# TestBench_rev2.net
KiCad netlist of a schematic drawn in EAGLE
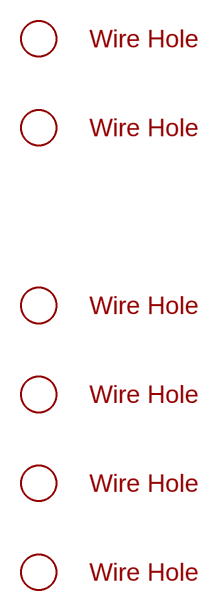
[diagram p0: schematic, sheet 1, part 1 of 2]
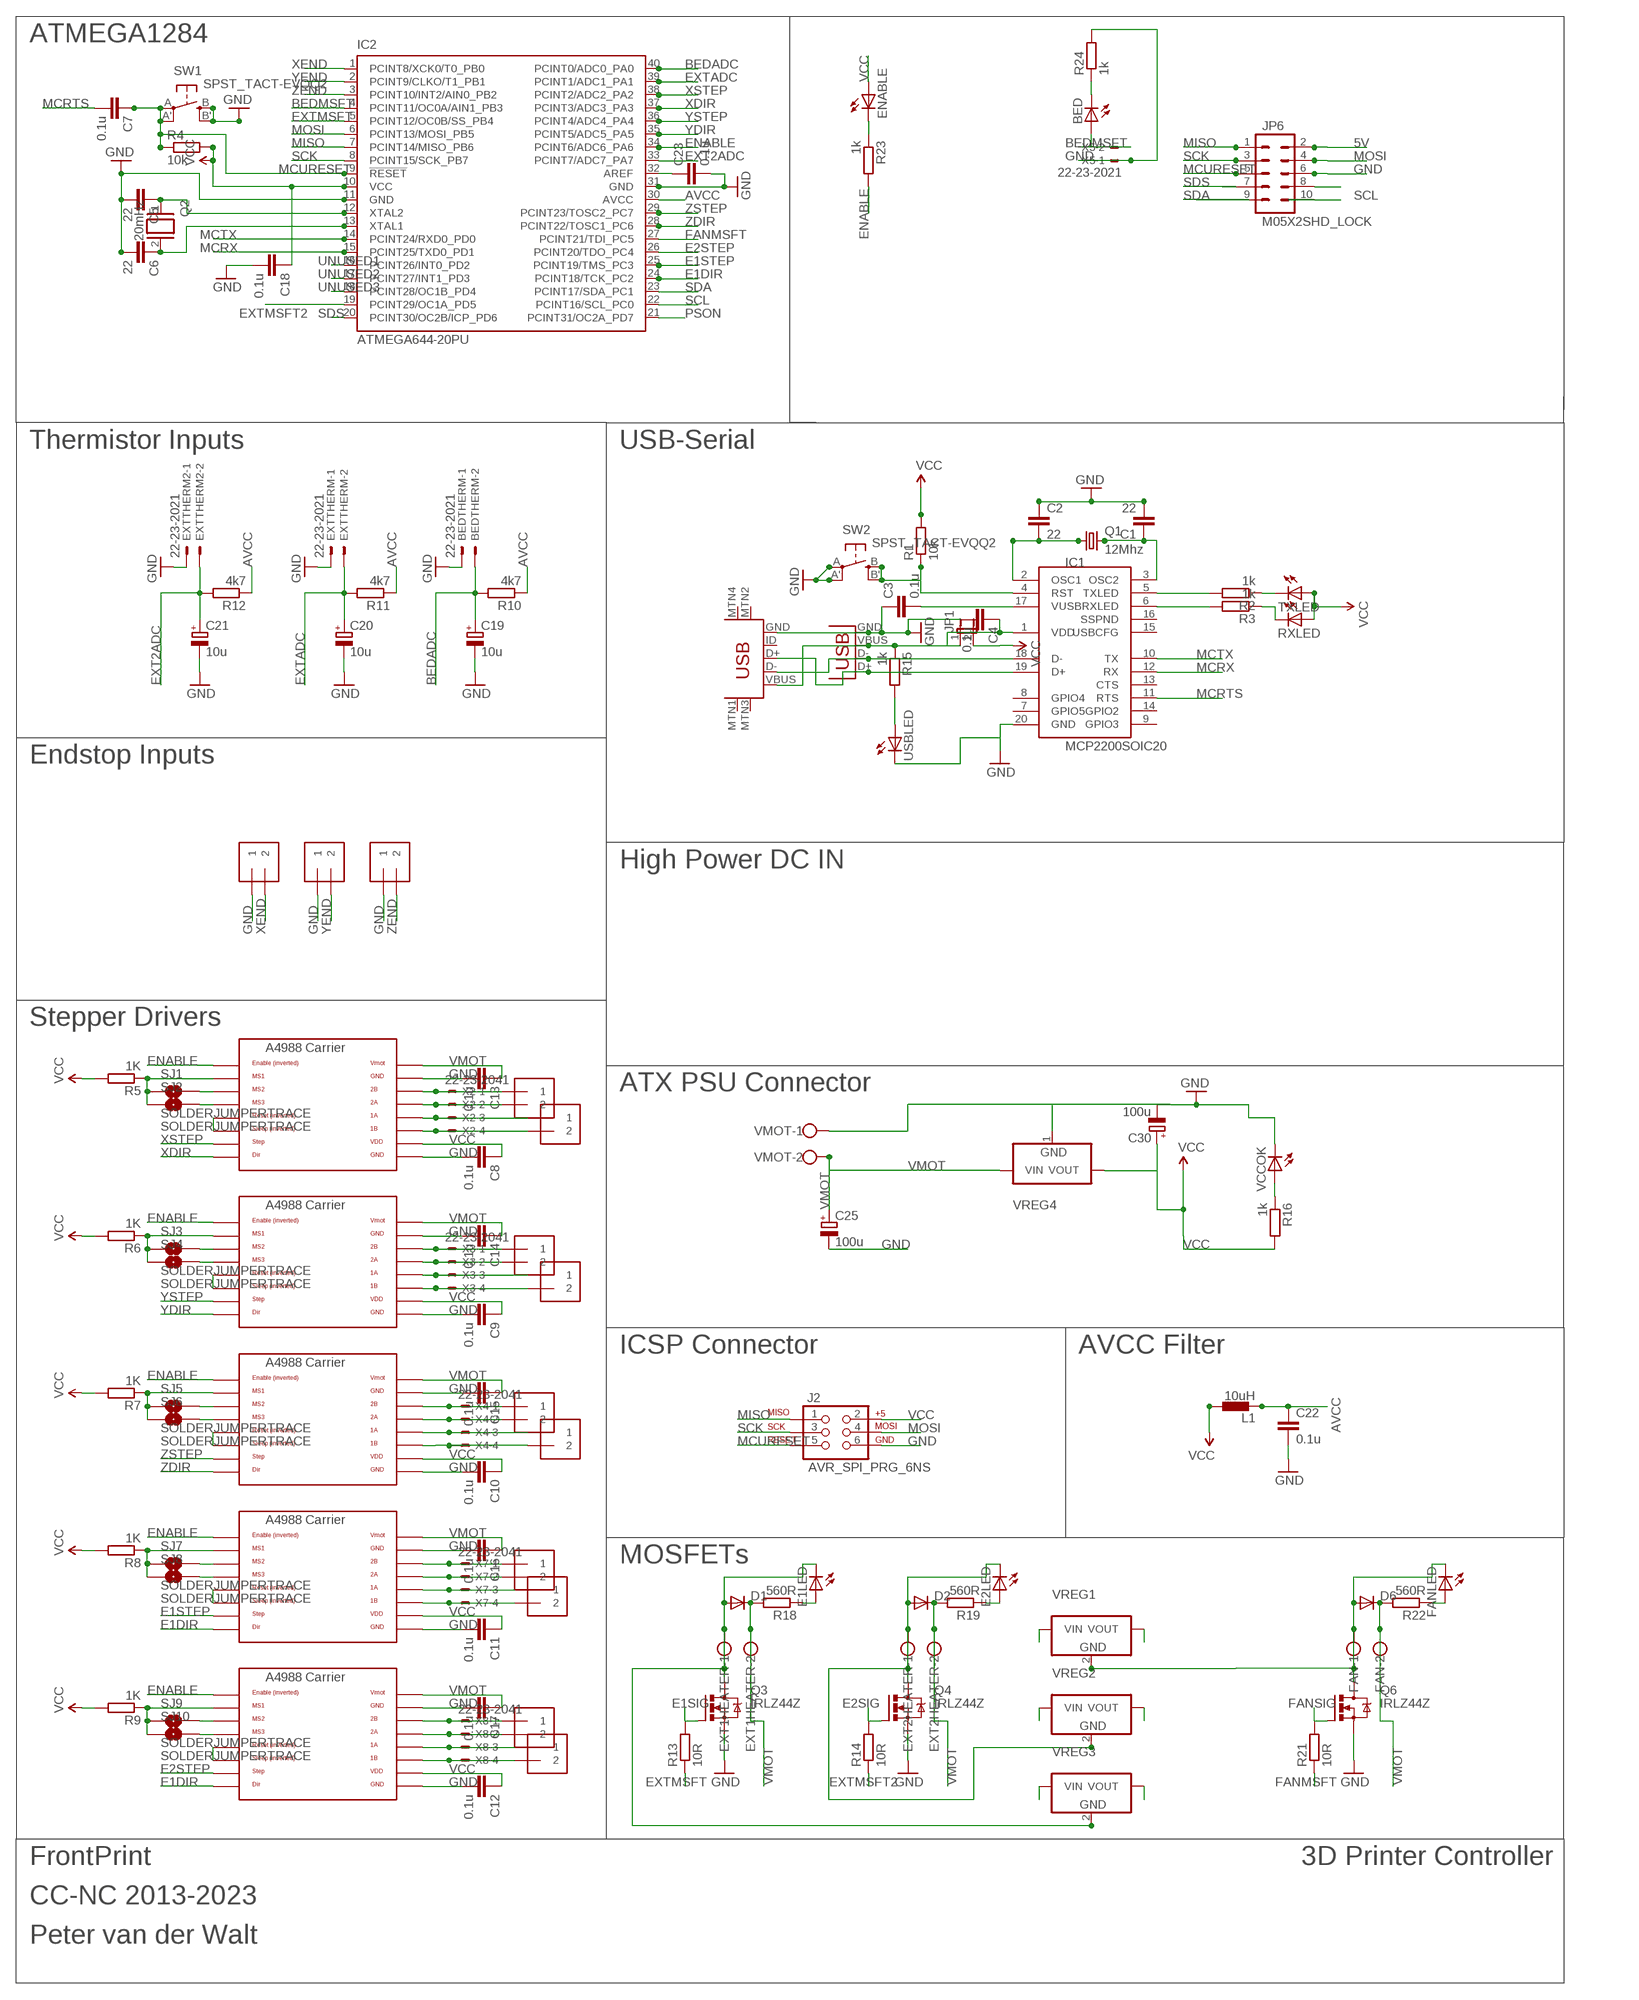
[diagram p1: schematic, sheet 1, part 2 of 2]

(export (version "E")
  (design (tool "Eeschema 10.0.6"))
  (components
    (comp (ref "BED")
      (value "LEDSMT1206")
      (footprint "eagle-import:1206")
      (libsource (lib "eagle-import") (part "LEDSMT1206"))
    )
    (comp (ref "BEDTHERM")
      (value "22-23-2021")
      (footprint "eagle-import:22-23-2021")
      (fields (field (name "MF") "MOLEX"))
      (libsource (lib "eagle-import") (part "22-23-2021"))
    )
    (comp (ref "C1")
      (value "22")
      (footprint "eagle-import:1206")
      (libsource (lib "eagle-import") (part "CAP1206"))
    )
    (comp (ref "C2")
      (value "22")
      (footprint "eagle-import:1206")
      (libsource (lib "eagle-import") (part "CAP1206"))
    )
    (comp (ref "C3")
      (value "0.1u")
      (footprint "eagle-import:1206")
      (libsource (lib "eagle-import") (part "CAP1206"))
    )
    (comp (ref "C4")
      (value "0.1u")
      (footprint "eagle-import:1206")
      (libsource (lib "eagle-import") (part "CAP1206"))
    )
    (comp (ref "C5")
      (value "22")
      (footprint "eagle-import:CAP-PTH-SMALL-KIT")
      (libsource (lib "eagle-import") (part "CAPKIT"))
    )
    (comp (ref "C6")
      (value "22")
      (footprint "eagle-import:CAP-PTH-SMALL-KIT")
      (libsource (lib "eagle-import") (part "CAPKIT"))
    )
    (comp (ref "C7")
      (value "0.1u")
      (footprint "eagle-import:1206")
      (libsource (lib "eagle-import") (part "CAP1206"))
    )
    (comp (ref "C8")
      (value "0.1u")
      (footprint "eagle-import:1206")
      (libsource (lib "eagle-import") (part "CAP1206"))
    )
    (comp (ref "C9")
      (value "0.1u")
      (footprint "eagle-import:1206")
      (libsource (lib "eagle-import") (part "CAP1206"))
    )
    (comp (ref "C10")
      (value "0.1u")
      (footprint "eagle-import:1206")
      (libsource (lib "eagle-import") (part "CAP1206"))
    )
    (comp (ref "C11")
      (value "0.1u")
      (footprint "eagle-import:1206")
      (libsource (lib "eagle-import") (part "CAP1206"))
    )
    (comp (ref "C12")
      (value "0.1u")
      (footprint "eagle-import:1206")
      (libsource (lib "eagle-import") (part "CAP1206"))
    )
    (comp (ref "C13")
      (value "0.1u")
      (footprint "eagle-import:1206")
      (libsource (lib "eagle-import") (part "CAP1206"))
    )
    (comp (ref "C14")
      (value "0.1u")
      (footprint "eagle-import:1206")
      (libsource (lib "eagle-import") (part "CAP1206"))
    )
    (comp (ref "C15")
      (value "0.1u")
      (footprint "eagle-import:1206")
      (libsource (lib "eagle-import") (part "CAP1206"))
    )
    (comp (ref "C16")
      (value "0.1u")
      (footprint "eagle-import:1206")
      (libsource (lib "eagle-import") (part "CAP1206"))
    )
    (comp (ref "C17")
      (value "0.1u")
      (footprint "eagle-import:1206")
      (libsource (lib "eagle-import") (part "CAP1206"))
    )
    (comp (ref "C18")
      (value "0.1u")
      (footprint "eagle-import:1206")
      (libsource (lib "eagle-import") (part "CAP1206"))
    )
    (comp (ref "C19")
      (value "10u")
      (footprint "eagle-import:E2,5-5")
      (libsource (lib "eagle-import") (part "CPOL-EUE2.5-5"))
    )
    (comp (ref "C20")
      (value "10u")
      (footprint "eagle-import:E2,5-5")
      (libsource (lib "eagle-import") (part "CPOL-EUE2.5-5"))
    )
    (comp (ref "C21")
      (value "10u")
      (footprint "eagle-import:E2,5-5")
      (libsource (lib "eagle-import") (part "CPOL-EUE2.5-5"))
    )
    (comp (ref "C22")
      (value "0.1u")
      (footprint "eagle-import:1206")
      (libsource (lib "eagle-import") (part "CAP1206"))
    )
    (comp (ref "C23")
      (value "0.1u")
      (footprint "eagle-import:1206")
      (libsource (lib "eagle-import") (part "CAP1206"))
    )
    (comp (ref "C25")
      (value "100u")
      (footprint "eagle-import:E5-8,5")
      (libsource (lib "eagle-import") (part "CPOL-EUE5-8.5"))
    )
    (comp (ref "C30")
      (value "100u")
      (footprint "eagle-import:E5-8,5")
      (libsource (lib "eagle-import") (part "CPOL-EUE5-8.5"))
    )
    (comp (ref "D1")
      (value "DIODE1N4148")
      (footprint "eagle-import:DIODE-1N4148")
      (libsource (lib "eagle-import") (part "DIODE1N4148"))
    )
    (comp (ref "D2")
      (value "DIODE1N4148")
      (footprint "eagle-import:DIODE-1N4148")
      (libsource (lib "eagle-import") (part "DIODE1N4148"))
    )
    (comp (ref "D6")
      (value "DIODE1N4148")
      (footprint "eagle-import:DIODE-1N4148")
      (libsource (lib "eagle-import") (part "DIODE1N4148"))
    )
    (comp (ref "E1LED")
      (value "LEDSMT1206")
      (footprint "eagle-import:1206")
      (libsource (lib "eagle-import") (part "LEDSMT1206"))
    )
    (comp (ref "E1MOT1")
      (value "1X2-3.5MM")
      (footprint "eagle-import:1X2-3.5MM")
      (libsource (lib "eagle-import") (part "1X2-3.5MM"))
    )
    (comp (ref "E1MOT2")
      (value "1X2-3.5MM")
      (footprint "eagle-import:1X2-3.5MM")
      (libsource (lib "eagle-import") (part "1X2-3.5MM"))
    )
    (comp (ref "E2LED")
      (value "LEDSMT1206")
      (footprint "eagle-import:1206")
      (libsource (lib "eagle-import") (part "LEDSMT1206"))
    )
    (comp (ref "E2MOT1")
      (value "1X2-3.5MM")
      (footprint "eagle-import:1X2-3.5MM")
      (libsource (lib "eagle-import") (part "1X2-3.5MM"))
    )
    (comp (ref "E2MOT2")
      (value "1X2-3.5MM")
      (footprint "eagle-import:1X2-3.5MM")
      (libsource (lib "eagle-import") (part "1X2-3.5MM"))
    )
    (comp (ref "ENABLE")
      (value "LEDSMT1206")
      (footprint "eagle-import:1206")
      (libsource (lib "eagle-import") (part "LEDSMT1206"))
    )
    (comp (ref "EPOLOLU")
      (value "POLOLU_A4983CARRIER")
      (footprint "eagle-import:A4988BREAKOUT")
      (libsource (lib "eagle-import") (part "POLOLU_A4983CARRIER"))
    )
    (comp (ref "EPOLOLU2")
      (value "POLOLU_A4983CARRIER")
      (footprint "eagle-import:A4988BREAKOUT")
      (libsource (lib "eagle-import") (part "POLOLU_A4983CARRIER"))
    )
    (comp (ref "EXT1HEATER")
      (value "W237-102")
      (footprint "eagle-import:W237-102")
      (fields (field (name "MPN") "237-102"))
      (libsource (lib "eagle-import") (part "W237-102"))
    )
    (comp (ref "EXT2HEATER")
      (value "W237-102")
      (footprint "eagle-import:W237-102")
      (fields (field (name "MPN") "237-102"))
      (libsource (lib "eagle-import") (part "W237-102"))
    )
    (comp (ref "EXTTHERM")
      (value "22-23-2021")
      (footprint "eagle-import:22-23-2021")
      (fields (field (name "MF") "MOLEX"))
      (libsource (lib "eagle-import") (part "22-23-2021"))
    )
    (comp (ref "EXTTHERM2")
      (value "22-23-2021")
      (footprint "eagle-import:22-23-2021")
      (fields (field (name "MF") "MOLEX"))
      (libsource (lib "eagle-import") (part "22-23-2021"))
    )
    (comp (ref "FAN")
      (value "W237-102")
      (footprint "eagle-import:W237-102")
      (fields (field (name "MPN") "237-102"))
      (libsource (lib "eagle-import") (part "W237-102"))
    )
    (comp (ref "FANLED")
      (value "LEDSMT1206")
      (footprint "eagle-import:1206")
      (libsource (lib "eagle-import") (part "LEDSMT1206"))
    )
    (comp (ref "IC1")
      (value "MCP2200SOIC20")
      (footprint "eagle-import:SOIC20")
      (libsource (lib "eagle-import") (part "MCP2200SOIC20"))
    )
    (comp (ref "IC2")
      (value "ATMEGA644-20PU")
      (footprint "eagle-import:DIL40")
      (libsource (lib "eagle-import") (part "ATMEGA644-PU20"))
    )
    (comp (ref "J2")
      (value "AVR_SPI_PRG_6NS")
      (footprint "eagle-import:2X3-NS")
      (libsource (lib "eagle-import") (part "AVR_SPI_PRG_6NS"))
    )
    (comp (ref "JP1")
      (value "JUMPER-2PTH_LOCK")
      (footprint "eagle-import:1X02_LOCK")
      (libsource (lib "eagle-import") (part "JUMPER-2PTH_LOCK"))
    )
    (comp (ref "JP6")
      (value "M05X2SHD_LOCK")
      (footprint "eagle-import:2X5-SHROUDED_LOCK")
      (libsource (lib "eagle-import") (part "M05X2SHD_LOCK"))
    )
    (comp (ref "L1")
      (value "10uH")
      (footprint "eagle-import:BL01RN1A")
      (libsource (lib "eagle-import") (part "BL01RN1A"))
    )
    (comp (ref "Q1")
      (value "12Mhz")
      (footprint "eagle-import:HC49UP")
      (libsource (lib "eagle-import") (part "CRYSTALHC49UP"))
    )
    (comp (ref "Q2")
      (value "20mHz")
      (footprint "eagle-import:QS")
      (libsource (lib "eagle-import") (part "XTAL/S"))
    )
    (comp (ref "Q3")
      (value "IRLZ44Z")
      (footprint "eagle-import:TO220BH")
      (libsource (lib "eagle-import") (part "IRLZ44Z"))
    )
    (comp (ref "Q4")
      (value "IRLZ44Z")
      (footprint "eagle-import:TO220BH")
      (libsource (lib "eagle-import") (part "IRLZ44Z"))
    )
    (comp (ref "Q6")
      (value "IRLZ44Z")
      (footprint "eagle-import:TO220BH")
      (libsource (lib "eagle-import") (part "IRLZ44Z"))
    )
    (comp (ref "R1")
      (value "10k")
      (footprint "eagle-import:M1206")
      (libsource (lib "eagle-import") (part "R-EU_M1206"))
    )
    (comp (ref "R2")
      (value "1k")
      (footprint "eagle-import:M1206")
      (libsource (lib "eagle-import") (part "R-EU_M1206"))
    )
    (comp (ref "R3")
      (value "1k")
      (footprint "eagle-import:M1206")
      (libsource (lib "eagle-import") (part "R-EU_M1206"))
    )
    (comp (ref "R4")
      (value "10k")
      (footprint "eagle-import:M1206")
      (libsource (lib "eagle-import") (part "R-EU_M1206"))
    )
    (comp (ref "R5")
      (value "1K")
      (footprint "eagle-import:M1206")
      (libsource (lib "eagle-import") (part "R-EU_M1206"))
    )
    (comp (ref "R6")
      (value "1K")
      (footprint "eagle-import:M1206")
      (libsource (lib "eagle-import") (part "R-EU_M1206"))
    )
    (comp (ref "R7")
      (value "1K")
      (footprint "eagle-import:M1206")
      (libsource (lib "eagle-import") (part "R-EU_M1206"))
    )
    (comp (ref "R8")
      (value "1K")
      (footprint "eagle-import:M1206")
      (libsource (lib "eagle-import") (part "R-EU_M1206"))
    )
    (comp (ref "R9")
      (value "1K")
      (footprint "eagle-import:M1206")
      (libsource (lib "eagle-import") (part "R-EU_M1206"))
    )
    (comp (ref "R10")
      (value "4k7")
      (footprint "eagle-import:M1206")
      (libsource (lib "eagle-import") (part "R-EU_M1206"))
    )
    (comp (ref "R11")
      (value "4k7")
      (footprint "eagle-import:M1206")
      (libsource (lib "eagle-import") (part "R-EU_M1206"))
    )
    (comp (ref "R12")
      (value "4k7")
      (footprint "eagle-import:M1206")
      (libsource (lib "eagle-import") (part "R-EU_M1206"))
    )
    (comp (ref "R13")
      (value "10R")
      (footprint "eagle-import:M1206")
      (libsource (lib "eagle-import") (part "R-EU_M1206"))
    )
    (comp (ref "R14")
      (value "10R")
      (footprint "eagle-import:M1206")
      (libsource (lib "eagle-import") (part "R-EU_M1206"))
    )
    (comp (ref "R15")
      (value "1k")
      (footprint "eagle-import:M1206")
      (libsource (lib "eagle-import") (part "R-EU_M1206"))
    )
    (comp (ref "R16")
      (value "1k")
      (footprint "eagle-import:M1206")
      (libsource (lib "eagle-import") (part "R-EU_M1206"))
    )
    (comp (ref "R18")
      (value "560R")
      (footprint "eagle-import:M1206")
      (libsource (lib "eagle-import") (part "R-EU_M1206"))
    )
    (comp (ref "R19")
      (value "560R")
      (footprint "eagle-import:M1206")
      (libsource (lib "eagle-import") (part "R-EU_M1206"))
    )
    (comp (ref "R21")
      (value "10R")
      (footprint "eagle-import:M1206")
      (libsource (lib "eagle-import") (part "R-EU_M1206"))
    )
    (comp (ref "R22")
      (value "560R")
      (footprint "eagle-import:M1206")
      (libsource (lib "eagle-import") (part "R-EU_M1206"))
    )
    (comp (ref "R23")
      (value "1k")
      (footprint "eagle-import:M1206")
      (libsource (lib "eagle-import") (part "R-EU_M1206"))
    )
    (comp (ref "R24")
      (value "1k")
      (footprint "eagle-import:M1206")
      (libsource (lib "eagle-import") (part "R-EU_M1206"))
    )
    (comp (ref "RXLED")
      (value "LEDSMT1206")
      (footprint "eagle-import:1206")
      (libsource (lib "eagle-import") (part "LEDSMT1206"))
    )
    (comp (ref "SJ1")
      (value "SOLDERJUMPERTRACE")
      (footprint "eagle-import:SJ_2S-TRACE")
      (libsource (lib "eagle-import") (part "SOLDERJUMPERTRACE"))
    )
    (comp (ref "SJ2")
      (value "SOLDERJUMPERTRACE")
      (footprint "eagle-import:SJ_2S-TRACE")
      (libsource (lib "eagle-import") (part "SOLDERJUMPERTRACE"))
    )
    (comp (ref "SJ3")
      (value "SOLDERJUMPERTRACE")
      (footprint "eagle-import:SJ_2S-TRACE")
      (libsource (lib "eagle-import") (part "SOLDERJUMPERTRACE"))
    )
    (comp (ref "SJ4")
      (value "SOLDERJUMPERTRACE")
      (footprint "eagle-import:SJ_2S-TRACE")
      (libsource (lib "eagle-import") (part "SOLDERJUMPERTRACE"))
    )
    (comp (ref "SJ5")
      (value "SOLDERJUMPERTRACE")
      (footprint "eagle-import:SJ_2S-TRACE")
      (libsource (lib "eagle-import") (part "SOLDERJUMPERTRACE"))
    )
    (comp (ref "SJ6")
      (value "SOLDERJUMPERTRACE")
      (footprint "eagle-import:SJ_2S-TRACE")
      (libsource (lib "eagle-import") (part "SOLDERJUMPERTRACE"))
    )
    (comp (ref "SJ7")
      (value "SOLDERJUMPERTRACE")
      (footprint "eagle-import:SJ_2S-TRACE")
      (libsource (lib "eagle-import") (part "SOLDERJUMPERTRACE"))
    )
    (comp (ref "SJ8")
      (value "SOLDERJUMPERTRACE")
      (footprint "eagle-import:SJ_2S-TRACE")
      (libsource (lib "eagle-import") (part "SOLDERJUMPERTRACE"))
    )
    (comp (ref "SJ9")
      (value "SOLDERJUMPERTRACE")
      (footprint "eagle-import:SJ_2S-TRACE")
      (libsource (lib "eagle-import") (part "SOLDERJUMPERTRACE"))
    )
    (comp (ref "SJ10")
      (value "SOLDERJUMPERTRACE")
      (footprint "eagle-import:SJ_2S-TRACE")
      (libsource (lib "eagle-import") (part "SOLDERJUMPERTRACE"))
    )
    (comp (ref "SW1")
      (value "SPST_TACT-EVQQ2")
      (footprint "eagle-import:EVQ-Q2")
      (libsource (lib "eagle-import") (part "SPST_TACT-EVQQ2"))
    )
    (comp (ref "SW2")
      (value "SPST_TACT-EVQQ2")
      (footprint "eagle-import:EVQ-Q2")
      (libsource (lib "eagle-import") (part "SPST_TACT-EVQQ2"))
    )
    (comp (ref "TXLED")
      (value "LEDSMT1206")
      (footprint "eagle-import:1206")
      (libsource (lib "eagle-import") (part "LEDSMT1206"))
    )
    (comp (ref "U$1")
      (value "3MMHOLE")
      (footprint "eagle-import:3MMHOLE")
      (libsource (lib "eagle-import") (part "3MMHOLE"))
    )
    (comp (ref "U$2")
      (value "USB-MINIB-5PIN")
      (footprint "eagle-import:USB-MINIB")
      (libsource (lib "eagle-import") (part "USB-MINIB-5PIN"))
    )
    (comp (ref "U$3")
      (value "3MMHOLE")
      (footprint "eagle-import:3MMHOLE")
      (libsource (lib "eagle-import") (part "3MMHOLE"))
    )
    (comp (ref "U$5")
      (value "3MMHOLE")
      (footprint "eagle-import:3MMHOLE")
      (libsource (lib "eagle-import") (part "3MMHOLE"))
    )
    (comp (ref "U$6")
      (value "3MMHOLE")
      (footprint "eagle-import:3MMHOLE")
      (libsource (lib "eagle-import") (part "3MMHOLE"))
    )
    (comp (ref "U$7")
      (value "3MMHOLE")
      (footprint "eagle-import:3MMHOLE")
      (libsource (lib "eagle-import") (part "3MMHOLE"))
    )
    (comp (ref "U$8")
      (value "3MMHOLE")
      (footprint "eagle-import:3MMHOLE")
      (libsource (lib "eagle-import") (part "3MMHOLE"))
    )
    (comp (ref "USBLED")
      (value "LEDSMT1206")
      (footprint "eagle-import:1206")
      (libsource (lib "eagle-import") (part "LEDSMT1206"))
    )
    (comp (ref "VCCOK")
      (value "LEDSMT1206")
      (footprint "eagle-import:1206")
      (libsource (lib "eagle-import") (part "LEDSMT1206"))
    )
    (comp (ref "VMOT")
      (value "W237-102")
      (footprint "eagle-import:W237-102")
      (fields
        (field (name "MPN") "237-102")
        (field (name "MPN_1") "237-102")
        (field (name "OC_FARNELL") "unknown")
        (field (name "OC_NEWARK") "70K9898")
      )
      (libsource (lib "eagle-import") (part "W237-102"))
    )
    (comp (ref "VREG1")
      (value "VREG_3PINS-D2PAK")
      (footprint "eagle-import:D2PAK")
      (libsource (lib "eagle-import") (part "VREG_3PINS-D2PAK"))
    )
    (comp (ref "VREG2")
      (value "VREG_3PINS-D2PAK")
      (footprint "eagle-import:D2PAK")
      (libsource (lib "eagle-import") (part "VREG_3PINS-D2PAK"))
    )
    (comp (ref "VREG3")
      (value "VREG_3PINS-D2PAK")
      (footprint "eagle-import:D2PAK")
      (libsource (lib "eagle-import") (part "VREG_3PINS-D2PAK"))
    )
    (comp (ref "VREG4")
      (value "VREG_3PINS-DPAK")
      (footprint "eagle-import:DPAK")
      (libsource (lib "eagle-import") (part "VREG_3PINS-DPAK"))
    )
    (comp (ref "X1")
      (value "USBPTH")
      (footprint "eagle-import:USB-B-PTH")
      (libsource (lib "eagle-import") (part "USBPTH"))
    )
    (comp (ref "X2")
      (value "22-23-2041")
      (footprint "eagle-import:22-23-2041")
      (fields (field (name "MF") "MOLEX"))
      (libsource (lib "eagle-import") (part "22-23-2041"))
    )
    (comp (ref "X3")
      (value "22-23-2041")
      (footprint "eagle-import:22-23-2041")
      (fields (field (name "MF") "MOLEX"))
      (libsource (lib "eagle-import") (part "22-23-2041"))
    )
    (comp (ref "X4")
      (value "22-23-2041")
      (footprint "eagle-import:22-23-2041")
      (fields (field (name "MF") "MOLEX"))
      (libsource (lib "eagle-import") (part "22-23-2041"))
    )
    (comp (ref "X5")
      (value "22-23-2021")
      (footprint "eagle-import:22-23-2021")
      (fields (field (name "MF") "MOLEX"))
      (libsource (lib "eagle-import") (part "22-23-2021"))
    )
    (comp (ref "X7")
      (value "22-23-2041")
      (footprint "eagle-import:22-23-2041")
      (fields (field (name "MF") "MOLEX"))
      (libsource (lib "eagle-import") (part "22-23-2041"))
    )
    (comp (ref "X8")
      (value "22-23-2041")
      (footprint "eagle-import:22-23-2041")
      (fields (field (name "MF") "MOLEX"))
      (libsource (lib "eagle-import") (part "22-23-2041"))
    )
    (comp (ref "XEND")
      (value "1X2-3.5MM")
      (footprint "eagle-import:1X2-3.5MM")
      (libsource (lib "eagle-import") (part "1X2-3.5MM"))
    )
    (comp (ref "XMOT1")
      (value "1X2-3.5MM")
      (footprint "eagle-import:1X2-3.5MM")
      (libsource (lib "eagle-import") (part "1X2-3.5MM"))
    )
    (comp (ref "XMOT2")
      (value "1X2-3.5MM")
      (footprint "eagle-import:1X2-3.5MM")
      (libsource (lib "eagle-import") (part "1X2-3.5MM"))
    )
    (comp (ref "XPOLOLU")
      (value "POLOLU_A4983CARRIER")
      (footprint "eagle-import:A4988BREAKOUT")
      (libsource (lib "eagle-import") (part "POLOLU_A4983CARRIER"))
    )
    (comp (ref "YEND")
      (value "1X2-3.5MM")
      (footprint "eagle-import:1X2-3.5MM")
      (libsource (lib "eagle-import") (part "1X2-3.5MM"))
    )
    (comp (ref "YMOT1")
      (value "1X2-3.5MM")
      (footprint "eagle-import:1X2-3.5MM")
      (libsource (lib "eagle-import") (part "1X2-3.5MM"))
    )
    (comp (ref "YMOT2")
      (value "1X2-3.5MM")
      (footprint "eagle-import:1X2-3.5MM")
      (libsource (lib "eagle-import") (part "1X2-3.5MM"))
    )
    (comp (ref "YPOLOLU")
      (value "POLOLU_A4983CARRIER")
      (footprint "eagle-import:A4988BREAKOUT")
      (libsource (lib "eagle-import") (part "POLOLU_A4983CARRIER"))
    )
    (comp (ref "ZEND")
      (value "1X2-3.5MM")
      (footprint "eagle-import:1X2-3.5MM")
      (libsource (lib "eagle-import") (part "1X2-3.5MM"))
    )
    (comp (ref "ZMOT1")
      (value "1X2-3.5MM")
      (footprint "eagle-import:1X2-3.5MM")
      (libsource (lib "eagle-import") (part "1X2-3.5MM"))
    )
    (comp (ref "ZMOT2")
      (value "1X2-3.5MM")
      (footprint "eagle-import:1X2-3.5MM")
      (libsource (lib "eagle-import") (part "1X2-3.5MM"))
    )
    (comp (ref "ZPOLOLU")
      (value "POLOLU_A4983CARRIER")
      (footprint "eagle-import:A4988BREAKOUT")
      (libsource (lib "eagle-import") (part "POLOLU_A4983CARRIER"))
    )
  )
  (nets
    (net (code "1") (name "/5V") (class "Default")
      (node (ref "JP6") (pin "2") (pinfunction "2_2") (pintype "passive"))
    )
    (net (code "2") (name "/AVCC") (class "Default")
      (node (ref "C22") (pin "1") (pinfunction "1_1") (pintype "passive"))
      (node (ref "IC2") (pin "30") (pinfunction "AVCC_30") (pintype "power_in"))
      (node (ref "L1") (pin "1") (pinfunction "1_1") (pintype "passive"))
      (node (ref "R10") (pin "1") (pinfunction "1_1") (pintype "passive"))
      (node (ref "R11") (pin "1") (pinfunction "1_1") (pintype "passive"))
      (node (ref "R12") (pin "1") (pinfunction "1_1") (pintype "passive"))
    )
    (net (code "3") (name "/BEDADC") (class "Default")
      (node (ref "BEDTHERM") (pin "2") (pinfunction "S_2") (pintype "passive"))
      (node (ref "C19") (pin "+") (pinfunction "+_+") (pintype "passive"))
      (node (ref "IC2") (pin "40") (pinfunction "PCINT0/ADC0_PA0_40") (pintype "bidirectional"))
      (node (ref "R10") (pin "2") (pinfunction "2_2") (pintype "passive"))
    )
    (net (code "4") (name "/BEDMSFT") (class "Default")
      (node (ref "BED") (pin "A") (pinfunction "A_A") (pintype "passive"))
      (node (ref "IC2") (pin "4") (pinfunction "PCINT11/OC0A/AIN1_PB3_4") (pintype "bidirectional"))
      (node (ref "X5") (pin "2") (pinfunction "S_2") (pintype "passive"))
    )
    (net (code "5") (name "/E1DIR") (class "Default")
      (node (ref "EPOLOLU") (pin "DIR") (pinfunction "DIR_DIR") (pintype "input"))
      (node (ref "EPOLOLU2") (pin "DIR") (pinfunction "DIR_DIR") (pintype "input"))
      (node (ref "IC2") (pin "24") (pinfunction "PCINT18/TCK_PC2_24") (pintype "bidirectional"))
    )
    (net (code "6") (name "/E1SIG") (class "Default")
      (node (ref "Q3") (pin "G") (pinfunction "G_G") (pintype "passive"))
      (node (ref "R13") (pin "2") (pinfunction "2_2") (pintype "passive"))
      (node (ref "VREG3") (pin "1") (pinfunction "VIN_1") (pintype "bidirectional"))
    )
    (net (code "7") (name "/E1STEP") (class "Default")
      (node (ref "EPOLOLU") (pin "STEP") (pinfunction "STEP_STEP") (pintype "input"))
      (node (ref "IC2") (pin "25") (pinfunction "PCINT19/TMS_PC3_25") (pintype "bidirectional"))
    )
    (net (code "8") (name "/E2SIG") (class "Default")
      (node (ref "Q4") (pin "G") (pinfunction "G_G") (pintype "passive"))
      (node (ref "R14") (pin "2") (pinfunction "2_2") (pintype "passive"))
      (node (ref "VREG2") (pin "1") (pinfunction "VIN_1") (pintype "bidirectional"))
    )
    (net (code "9") (name "/E2STEP") (class "Default")
      (node (ref "EPOLOLU2") (pin "STEP") (pinfunction "STEP_STEP") (pintype "input"))
      (node (ref "IC2") (pin "26") (pinfunction "PCINT20/TDO_PC4_26") (pintype "bidirectional"))
    )
    (net (code "10") (name "/ENABLE") (class "Default")
      (node (ref "EPOLOLU") (pin "EN") (pinfunction "EN_EN") (pintype "input"))
      (node (ref "EPOLOLU2") (pin "EN") (pinfunction "EN_EN") (pintype "input"))
      (node (ref "IC2") (pin "34") (pinfunction "PCINT6/ADC6_PA6_34") (pintype "bidirectional"))
      (node (ref "R23") (pin "2") (pinfunction "2_2") (pintype "passive"))
      (node (ref "XPOLOLU") (pin "EN") (pinfunction "EN_EN") (pintype "input"))
      (node (ref "YPOLOLU") (pin "EN") (pinfunction "EN_EN") (pintype "input"))
      (node (ref "ZPOLOLU") (pin "EN") (pinfunction "EN_EN") (pintype "input"))
    )
    (net (code "11") (name "/EXT2ADC") (class "Default")
      (node (ref "C21") (pin "+") (pinfunction "+_+") (pintype "passive"))
      (node (ref "EXTTHERM2") (pin "2") (pinfunction "S_2") (pintype "passive"))
      (node (ref "IC2") (pin "33") (pinfunction "PCINT7/ADC7_PA7_33") (pintype "bidirectional"))
      (node (ref "R12") (pin "2") (pinfunction "2_2") (pintype "passive"))
    )
    (net (code "12") (name "/EXTADC") (class "Default")
      (node (ref "C20") (pin "+") (pinfunction "+_+") (pintype "passive"))
      (node (ref "EXTTHERM") (pin "2") (pinfunction "S_2") (pintype "passive"))
      (node (ref "IC2") (pin "39") (pinfunction "PCINT1/ADC1_PA1_39") (pintype "bidirectional"))
      (node (ref "R11") (pin "2") (pinfunction "2_2") (pintype "passive"))
    )
    (net (code "13") (name "/EXTMSFT") (class "Default")
      (node (ref "IC2") (pin "5") (pinfunction "PCINT12/OC0B/SS_PB4_5") (pintype "bidirectional"))
      (node (ref "R13") (pin "1") (pinfunction "1_1") (pintype "passive"))
    )
    (net (code "14") (name "/EXTMSFT2") (class "Default")
      (node (ref "IC2") (pin "19") (pinfunction "PCINT29/OC1A_PD5_19") (pintype "bidirectional"))
      (node (ref "R14") (pin "1") (pinfunction "1_1") (pintype "passive"))
    )
    (net (code "15") (name "/FANMSFT") (class "Default")
      (node (ref "IC2") (pin "27") (pinfunction "PCINT21/TDI_PC5_27") (pintype "bidirectional"))
      (node (ref "R21") (pin "1") (pinfunction "1_1") (pintype "passive"))
    )
    (net (code "16") (name "/FANSIG") (class "Default")
      (node (ref "Q6") (pin "G") (pinfunction "G_G") (pintype "passive"))
      (node (ref "R21") (pin "2") (pinfunction "2_2") (pintype "passive"))
      (node (ref "VREG1") (pin "1") (pinfunction "VIN_1") (pintype "bidirectional"))
    )
    (net (code "17") (name "/MCRTS") (class "Default")
      (node (ref "C7") (pin "2") (pinfunction "2_2") (pintype "passive"))
      (node (ref "IC1") (pin "11") (pinfunction "RTS_11") (pintype "bidirectional"))
    )
    (net (code "18") (name "/MCRX") (class "Default")
      (node (ref "IC1") (pin "12") (pinfunction "RX_12") (pintype "bidirectional"))
      (node (ref "IC2") (pin "15") (pinfunction "PCINT25/TXD0_PD1_15") (pintype "bidirectional"))
    )
    (net (code "19") (name "/MCTX") (class "Default")
      (node (ref "IC1") (pin "10") (pinfunction "TX_10") (pintype "bidirectional"))
      (node (ref "IC2") (pin "14") (pinfunction "PCINT24/RXD0_PD0_14") (pintype "bidirectional"))
    )
    (net (code "20") (name "/MCURESET") (class "Default")
      (node (ref "C7") (pin "1") (pinfunction "1_1") (pintype "passive"))
      (node (ref "IC2") (pin "9") (pinfunction "~{RESET}_9") (pintype "input"))
      (node (ref "J2") (pin "5") (pinfunction "5_5") (pintype "passive"))
      (node (ref "JP6") (pin "5") (pinfunction "5_5") (pintype "passive"))
      (node (ref "R4") (pin "1") (pinfunction "1_1") (pintype "passive"))
      (node (ref "SW1") (pin "A") (pinfunction "P_A") (pintype "passive"))
      (node (ref "SW1") (pin "A'") (pinfunction "P1_A'") (pintype "passive"))
    )
    (net (code "21") (name "/MISO") (class "Default")
      (node (ref "IC2") (pin "7") (pinfunction "PCINT14/MISO_PB6_7") (pintype "bidirectional"))
      (node (ref "J2") (pin "1") (pinfunction "1_1") (pintype "passive"))
      (node (ref "JP6") (pin "1") (pinfunction "1_1") (pintype "passive"))
    )
    (net (code "22") (name "/MOSI") (class "Default")
      (node (ref "IC2") (pin "6") (pinfunction "PCINT13/MOSI_PB5_6") (pintype "bidirectional"))
      (node (ref "J2") (pin "4") (pinfunction "4_4") (pintype "passive"))
      (node (ref "JP6") (pin "4") (pinfunction "4_4") (pintype "passive"))
    )
    (net (code "23") (name "/PSON") (class "Default")
      (node (ref "IC2") (pin "21") (pinfunction "PCINT31/OC2A_PD7_21") (pintype "bidirectional"))
    )
    (net (code "24") (name "/SCK") (class "Default")
      (node (ref "IC2") (pin "8") (pinfunction "PCINT15/SCK_PB7_8") (pintype "bidirectional"))
      (node (ref "J2") (pin "3") (pinfunction "3_3") (pintype "passive"))
      (node (ref "JP6") (pin "3") (pinfunction "3_3") (pintype "passive"))
    )
    (net (code "25") (name "/SCL") (class "Default")
      (node (ref "IC2") (pin "22") (pinfunction "PCINT16/SCL_PC0_22") (pintype "bidirectional"))
      (node (ref "JP6") (pin "10") (pinfunction "10_10") (pintype "passive"))
    )
    (net (code "26") (name "/SDA") (class "Default")
      (node (ref "IC2") (pin "23") (pinfunction "PCINT17/SDA_PC1_23") (pintype "bidirectional"))
      (node (ref "JP6") (pin "9") (pinfunction "9_9") (pintype "passive"))
    )
    (net (code "27") (name "/SDS") (class "Default")
      (node (ref "IC2") (pin "20") (pinfunction "PCINT30/OC2B/ICP_PD6_20") (pintype "bidirectional"))
      (node (ref "JP6") (pin "7") (pinfunction "7_7") (pintype "passive"))
    )
    (net (code "28") (name "/UNUSED1") (class "Default")
      (node (ref "IC2") (pin "16") (pinfunction "PCINT26/INT0_PD2_16") (pintype "bidirectional"))
    )
    (net (code "29") (name "/UNUSED2") (class "Default")
      (node (ref "IC2") (pin "17") (pinfunction "PCINT27/INT1_PD3_17") (pintype "bidirectional"))
    )
    (net (code "30") (name "/UNUSED3") (class "Default")
      (node (ref "IC2") (pin "18") (pinfunction "PCINT28/OC1B_PD4_18") (pintype "bidirectional"))
    )
    (net (code "31") (name "/VMOT") (class "Default")
      (node (ref "C13") (pin "1") (pinfunction "1_1") (pintype "passive"))
      (node (ref "C14") (pin "1") (pinfunction "1_1") (pintype "passive"))
      (node (ref "C15") (pin "1") (pinfunction "1_1") (pintype "passive"))
      (node (ref "C16") (pin "1") (pinfunction "1_1") (pintype "passive"))
      (node (ref "C17") (pin "1") (pinfunction "1_1") (pintype "passive"))
      (node (ref "C25") (pin "+") (pinfunction "+_+") (pintype "passive"))
      (node (ref "D1") (pin "C") (pinfunction "C_C") (pintype "passive"))
      (node (ref "D2") (pin "C") (pinfunction "C_C") (pintype "passive"))
      (node (ref "D6") (pin "C") (pinfunction "C_C") (pintype "passive"))
      (node (ref "EPOLOLU") (pin "VMOT") (pinfunction "VMOT_VMOT") (pintype "power_in"))
      (node (ref "EPOLOLU2") (pin "VMOT") (pinfunction "VMOT_VMOT") (pintype "power_in"))
      (node (ref "EXT1HEATER") (pin "2") (pinfunction "KL_2") (pintype "passive"))
      (node (ref "EXT2HEATER") (pin "2") (pinfunction "KL_2") (pintype "passive"))
      (node (ref "FAN") (pin "2") (pinfunction "KL_2") (pintype "passive"))
      (node (ref "R18") (pin "2") (pinfunction "2_2") (pintype "passive"))
      (node (ref "R19") (pin "2") (pinfunction "2_2") (pintype "passive"))
      (node (ref "R22") (pin "2") (pinfunction "2_2") (pintype "passive"))
      (node (ref "VMOT") (pin "2") (pinfunction "KL_2") (pintype "passive"))
      (node (ref "VREG4") (pin "3") (pinfunction "VIN_3") (pintype "bidirectional"))
      (node (ref "XPOLOLU") (pin "VMOT") (pinfunction "VMOT_VMOT") (pintype "power_in"))
      (node (ref "YPOLOLU") (pin "VMOT") (pinfunction "VMOT_VMOT") (pintype "power_in"))
      (node (ref "ZPOLOLU") (pin "VMOT") (pinfunction "VMOT_VMOT") (pintype "power_in"))
    )
    (net (code "32") (name "/XDIR") (class "Default")
      (node (ref "IC2") (pin "37") (pinfunction "PCINT3/ADC3_PA3_37") (pintype "bidirectional"))
      (node (ref "XPOLOLU") (pin "DIR") (pinfunction "DIR_DIR") (pintype "input"))
    )
    (net (code "33") (name "/XEND") (class "Default")
      (node (ref "IC2") (pin "1") (pinfunction "PCINT8/XCK0/T0_PB0_1") (pintype "bidirectional"))
      (node (ref "XEND") (pin "2") (pinfunction "2_2") (pintype "passive"))
    )
    (net (code "34") (name "/XSTEP") (class "Default")
      (node (ref "IC2") (pin "38") (pinfunction "PCINT2/ADC2_PA2_38") (pintype "bidirectional"))
      (node (ref "XPOLOLU") (pin "STEP") (pinfunction "STEP_STEP") (pintype "input"))
    )
    (net (code "35") (name "/YDIR") (class "Default")
      (node (ref "IC2") (pin "35") (pinfunction "PCINT5/ADC5_PA5_35") (pintype "bidirectional"))
      (node (ref "YPOLOLU") (pin "DIR") (pinfunction "DIR_DIR") (pintype "input"))
    )
    (net (code "36") (name "/YEND") (class "Default")
      (node (ref "IC2") (pin "2") (pinfunction "PCINT9/CLKO/T1_PB1_2") (pintype "bidirectional"))
      (node (ref "YEND") (pin "2") (pinfunction "2_2") (pintype "passive"))
    )
    (net (code "37") (name "/YSTEP") (class "Default")
      (node (ref "IC2") (pin "36") (pinfunction "PCINT4/ADC4_PA4_36") (pintype "bidirectional"))
      (node (ref "YPOLOLU") (pin "STEP") (pinfunction "STEP_STEP") (pintype "input"))
    )
    (net (code "38") (name "/ZDIR") (class "Default")
      (node (ref "IC2") (pin "28") (pinfunction "PCINT22/TOSC1_PC6_28") (pintype "bidirectional"))
      (node (ref "ZPOLOLU") (pin "DIR") (pinfunction "DIR_DIR") (pintype "input"))
    )
    (net (code "39") (name "/ZEND") (class "Default")
      (node (ref "IC2") (pin "3") (pinfunction "PCINT10/INT2/AIN0_PB2_3") (pintype "bidirectional"))
      (node (ref "ZEND") (pin "2") (pinfunction "2_2") (pintype "passive"))
    )
    (net (code "40") (name "/ZSTEP") (class "Default")
      (node (ref "IC2") (pin "29") (pinfunction "PCINT23/TOSC2_PC7_29") (pintype "bidirectional"))
      (node (ref "ZPOLOLU") (pin "STEP") (pinfunction "STEP_STEP") (pintype "input"))
    )
    (net (code "41") (name "GND") (class "Default")
      (node (ref "BEDTHERM") (pin "1") (pinfunction "S_1") (pintype "passive"))
      (node (ref "C1") (pin "2") (pinfunction "2_2") (pintype "passive"))
      (node (ref "C10") (pin "2") (pinfunction "2_2") (pintype "passive"))
      (node (ref "C11") (pin "2") (pinfunction "2_2") (pintype "passive"))
      (node (ref "C12") (pin "2") (pinfunction "2_2") (pintype "passive"))
      (node (ref "C13") (pin "2") (pinfunction "2_2") (pintype "passive"))
      (node (ref "C14") (pin "2") (pinfunction "2_2") (pintype "passive"))
      (node (ref "C15") (pin "2") (pinfunction "2_2") (pintype "passive"))
      (node (ref "C16") (pin "2") (pinfunction "2_2") (pintype "passive"))
      (node (ref "C17") (pin "2") (pinfunction "2_2") (pintype "passive"))
      (node (ref "C18") (pin "2") (pinfunction "2_2") (pintype "passive"))
      (node (ref "C19") (pin "-") (pinfunction "-_-") (pintype "passive"))
      (node (ref "C2") (pin "1") (pinfunction "1_1") (pintype "passive"))
      (node (ref "C20") (pin "-") (pinfunction "-_-") (pintype "passive"))
      (node (ref "C21") (pin "-") (pinfunction "-_-") (pintype "passive"))
      (node (ref "C22") (pin "2") (pinfunction "2_2") (pintype "passive"))
      (node (ref "C23") (pin "2") (pinfunction "2_2") (pintype "passive"))
      (node (ref "C25") (pin "-") (pinfunction "-_-") (pintype "passive"))
      (node (ref "C3") (pin "1") (pinfunction "1_1") (pintype "passive"))
      (node (ref "C30") (pin "-") (pinfunction "-_-") (pintype "passive"))
      (node (ref "C4") (pin "2") (pinfunction "2_2") (pintype "passive"))
      (node (ref "C5") (pin "2") (pinfunction "2_2") (pintype "passive"))
      (node (ref "C6") (pin "2") (pinfunction "2_2") (pintype "passive"))
      (node (ref "C8") (pin "2") (pinfunction "2_2") (pintype "passive"))
      (node (ref "C9") (pin "2") (pinfunction "2_2") (pintype "passive"))
      (node (ref "EPOLOLU") (pin "GND") (pinfunction "GND_GND") (pintype "power_in"))
      (node (ref "EPOLOLU") (pin "GND@0") (pinfunction "GND_GND@0") (pintype "power_in"))
      (node (ref "EPOLOLU2") (pin "GND") (pinfunction "GND_GND") (pintype "power_in"))
      (node (ref "EPOLOLU2") (pin "GND@0") (pinfunction "GND_GND@0") (pintype "power_in"))
      (node (ref "EXTTHERM") (pin "1") (pinfunction "S_1") (pintype "passive"))
      (node (ref "EXTTHERM2") (pin "1") (pinfunction "S_1") (pintype "passive"))
      (node (ref "IC1") (pin "20") (pinfunction "GND_20") (pintype "bidirectional"))
      (node (ref "IC2") (pin "11") (pinfunction "GND_11") (pintype "power_in"))
      (node (ref "IC2") (pin "31") (pinfunction "GND_31") (pintype "power_in"))
      (node (ref "J2") (pin "6") (pinfunction "6_6") (pintype "passive"))
      (node (ref "JP6") (pin "6") (pinfunction "6_6") (pintype "passive"))
      (node (ref "Q3") (pin "S") (pinfunction "S_S") (pintype "passive"))
      (node (ref "Q4") (pin "S") (pinfunction "S_S") (pintype "passive"))
      (node (ref "Q6") (pin "S") (pinfunction "S_S") (pintype "passive"))
      (node (ref "R24") (pin "2") (pinfunction "2_2") (pintype "passive"))
      (node (ref "SW1") (pin "B") (pinfunction "S_B") (pintype "passive"))
      (node (ref "SW1") (pin "B'") (pinfunction "S1_B'") (pintype "passive"))
      (node (ref "SW2") (pin "A") (pinfunction "P_A") (pintype "passive"))
      (node (ref "SW2") (pin "A'") (pinfunction "P1_A'") (pintype "passive"))
      (node (ref "U$2") (pin "GND") (pinfunction "GND_GND") (pintype "bidirectional"))
      (node (ref "USBLED") (pin "C") (pinfunction "C_C") (pintype "passive"))
      (node (ref "VCCOK") (pin "C") (pinfunction "C_C") (pintype "passive"))
      (node (ref "VMOT") (pin "1") (pinfunction "KL_1") (pintype "passive"))
      (node (ref "VREG1") (pin "3") (pinfunction "VOUT_3") (pintype "bidirectional"))
      (node (ref "VREG2") (pin "3") (pinfunction "VOUT_3") (pintype "bidirectional"))
      (node (ref "VREG3") (pin "3") (pinfunction "VOUT_3") (pintype "bidirectional"))
      (node (ref "VREG4") (pin "1") (pinfunction "GND_1") (pintype "bidirectional"))
      (node (ref "X1") (pin "GND") (pinfunction "GND_GND") (pintype "bidirectional"))
      (node (ref "X5") (pin "1") (pinfunction "S_1") (pintype "passive"))
      (node (ref "XEND") (pin "1") (pinfunction "1_1") (pintype "passive"))
      (node (ref "XPOLOLU") (pin "GND") (pinfunction "GND_GND") (pintype "power_in"))
      (node (ref "XPOLOLU") (pin "GND@0") (pinfunction "GND_GND@0") (pintype "power_in"))
      (node (ref "YEND") (pin "1") (pinfunction "1_1") (pintype "passive"))
      (node (ref "YPOLOLU") (pin "GND") (pinfunction "GND_GND") (pintype "power_in"))
      (node (ref "YPOLOLU") (pin "GND@0") (pinfunction "GND_GND@0") (pintype "power_in"))
      (node (ref "ZEND") (pin "1") (pinfunction "1_1") (pintype "passive"))
      (node (ref "ZPOLOLU") (pin "GND") (pinfunction "GND_GND") (pintype "power_in"))
      (node (ref "ZPOLOLU") (pin "GND@0") (pinfunction "GND_GND@0") (pintype "power_in"))
    )
    (net (code "42") (name "Net-(BED-PadC)") (class "Default")
      (node (ref "BED") (pin "C") (pinfunction "C_C") (pintype "passive"))
      (node (ref "R24") (pin "1") (pinfunction "1_1") (pintype "passive"))
    )
    (net (code "43") (name "Net-(E1LED-PadA)") (class "Default")
      (node (ref "E1LED") (pin "A") (pinfunction "A_A") (pintype "passive"))
      (node (ref "R18") (pin "1") (pinfunction "1_1") (pintype "passive"))
    )
    (net (code "44") (name "Net-(E2LED-PadA)") (class "Default")
      (node (ref "E2LED") (pin "A") (pinfunction "A_A") (pintype "passive"))
      (node (ref "R19") (pin "1") (pinfunction "1_1") (pintype "passive"))
    )
    (net (code "45") (name "Net-(ENABLE-PadC)") (class "Default")
      (node (ref "ENABLE") (pin "C") (pinfunction "C_C") (pintype "passive"))
      (node (ref "R23") (pin "1") (pinfunction "1_1") (pintype "passive"))
    )
    (net (code "46") (name "Net-(EPOLOLU-PadMS1)") (class "Default")
      (node (ref "EPOLOLU") (pin "MS1") (pinfunction "MS1_MS1") (pintype "input"))
      (node (ref "R8") (pin "1") (pinfunction "1_1") (pintype "passive"))
      (node (ref "SJ7") (pin "1") (pinfunction "1_1") (pintype "passive"))
      (node (ref "SJ8") (pin "1") (pinfunction "1_1") (pintype "passive"))
    )
    (net (code "47") (name "Net-(EPOLOLU-PadMS2)") (class "Default")
      (node (ref "EPOLOLU") (pin "MS2") (pinfunction "MS2_MS2") (pintype "input"))
      (node (ref "SJ7") (pin "2") (pinfunction "2_2") (pintype "passive"))
    )
    (net (code "48") (name "Net-(EPOLOLU-PadMS3)") (class "Default")
      (node (ref "EPOLOLU") (pin "MS3") (pinfunction "MS3_MS3") (pintype "input"))
      (node (ref "SJ8") (pin "2") (pinfunction "2_2") (pintype "passive"))
    )
    (net (code "49") (name "Net-(EPOLOLU-SLEEP)") (class "Default")
      (node (ref "EPOLOLU") (pin "RST") (pinfunction "RST_RST") (pintype "input"))
      (node (ref "EPOLOLU") (pin "SLP") (pinfunction "SLEEP_SLP") (pintype "input"))
    )
    (net (code "50") (name "Net-(EPOLOLU2-PadMS1)") (class "Default")
      (node (ref "EPOLOLU2") (pin "MS1") (pinfunction "MS1_MS1") (pintype "input"))
      (node (ref "R9") (pin "1") (pinfunction "1_1") (pintype "passive"))
      (node (ref "SJ10") (pin "1") (pinfunction "1_1") (pintype "passive"))
      (node (ref "SJ9") (pin "1") (pinfunction "1_1") (pintype "passive"))
    )
    (net (code "51") (name "Net-(EPOLOLU2-PadMS2)") (class "Default")
      (node (ref "EPOLOLU2") (pin "MS2") (pinfunction "MS2_MS2") (pintype "input"))
      (node (ref "SJ9") (pin "2") (pinfunction "2_2") (pintype "passive"))
    )
    (net (code "52") (name "Net-(EPOLOLU2-PadMS3)") (class "Default")
      (node (ref "EPOLOLU2") (pin "MS3") (pinfunction "MS3_MS3") (pintype "input"))
      (node (ref "SJ10") (pin "2") (pinfunction "2_2") (pintype "passive"))
    )
    (net (code "53") (name "Net-(EPOLOLU2-SLEEP)") (class "Default")
      (node (ref "EPOLOLU2") (pin "RST") (pinfunction "RST_RST") (pintype "input"))
      (node (ref "EPOLOLU2") (pin "SLP") (pinfunction "SLEEP_SLP") (pintype "input"))
    )
    (net (code "54") (name "Net-(EXT1HEATERA-KL)") (class "Default")
      (node (ref "D1") (pin "A") (pinfunction "A_A") (pintype "passive"))
      (node (ref "E1LED") (pin "C") (pinfunction "C_C") (pintype "passive"))
      (node (ref "EXT1HEATER") (pin "1") (pinfunction "KL_1") (pintype "passive"))
      (node (ref "Q3") (pin "D") (pinfunction "D_D") (pintype "passive"))
      (node (ref "VREG3") (pin "2") (pinfunction "GND_2") (pintype "bidirectional"))
    )
    (net (code "55") (name "Net-(EXT2HEATERA-KL)") (class "Default")
      (node (ref "D2") (pin "A") (pinfunction "A_A") (pintype "passive"))
      (node (ref "E2LED") (pin "C") (pinfunction "C_C") (pintype "passive"))
      (node (ref "EXT2HEATER") (pin "1") (pinfunction "KL_1") (pintype "passive"))
      (node (ref "Q4") (pin "D") (pinfunction "D_D") (pintype "passive"))
      (node (ref "VREG2") (pin "2") (pinfunction "GND_2") (pintype "bidirectional"))
    )
    (net (code "56") (name "Net-(FANA-KL)") (class "Default")
      (node (ref "D6") (pin "A") (pinfunction "A_A") (pintype "passive"))
      (node (ref "FAN") (pin "1") (pinfunction "KL_1") (pintype "passive"))
      (node (ref "FANLED") (pin "C") (pinfunction "C_C") (pintype "passive"))
      (node (ref "Q6") (pin "D") (pinfunction "D_D") (pintype "passive"))
      (node (ref "VREG1") (pin "2") (pinfunction "GND_2") (pintype "bidirectional"))
    )
    (net (code "57") (name "Net-(FANLED-PadA)") (class "Default")
      (node (ref "FANLED") (pin "A") (pinfunction "A_A") (pintype "passive"))
      (node (ref "R22") (pin "1") (pinfunction "1_1") (pintype "passive"))
    )
    (net (code "58") (name "Net-(IC1-D+)") (class "Default")
      (node (ref "IC1") (pin "19") (pinfunction "D+_19") (pintype "bidirectional"))
      (node (ref "U$2") (pin "D+") (pinfunction "D+_D+") (pintype "bidirectional"))
      (node (ref "X1") (pin "D+") (pinfunction "D+_D+") (pintype "bidirectional"))
    )
    (net (code "59") (name "Net-(IC1-D-)") (class "Default")
      (node (ref "IC1") (pin "18") (pinfunction "D-_18") (pintype "bidirectional"))
      (node (ref "U$2") (pin "D-") (pinfunction "D-_D-") (pintype "bidirectional"))
      (node (ref "X1") (pin "D-") (pinfunction "D-_D-") (pintype "bidirectional"))
    )
    (net (code "60") (name "Net-(IC1-OSC1)") (class "Default")
      (node (ref "C2") (pin "2") (pinfunction "2_2") (pintype "passive"))
      (node (ref "IC1") (pin "2") (pinfunction "OSC1_2") (pintype "bidirectional"))
      (node (ref "Q1") (pin "1") (pinfunction "1_1") (pintype "passive"))
    )
    (net (code "61") (name "Net-(IC1-OSC2)") (class "Default")
      (node (ref "C1") (pin "1") (pinfunction "1_1") (pintype "passive"))
      (node (ref "IC1") (pin "3") (pinfunction "OSC2_3") (pintype "bidirectional"))
      (node (ref "Q1") (pin "2") (pinfunction "2_2") (pintype "passive"))
    )
    (net (code "62") (name "Net-(IC1-RST)") (class "Default")
      (node (ref "IC1") (pin "4") (pinfunction "RST_4") (pintype "bidirectional"))
      (node (ref "R1") (pin "1") (pinfunction "1_1") (pintype "passive"))
      (node (ref "SW2") (pin "B") (pinfunction "S_B") (pintype "passive"))
      (node (ref "SW2") (pin "B'") (pinfunction "S1_B'") (pintype "passive"))
    )
    (net (code "63") (name "Net-(IC1-RXLED)") (class "Default")
      (node (ref "IC1") (pin "6") (pinfunction "RXLED_6") (pintype "bidirectional"))
      (node (ref "R3") (pin "2") (pinfunction "2_2") (pintype "passive"))
    )
    (net (code "64") (name "Net-(IC1-TXLED)") (class "Default")
      (node (ref "IC1") (pin "5") (pinfunction "TXLED_5") (pintype "bidirectional"))
      (node (ref "R2") (pin "2") (pinfunction "2_2") (pintype "passive"))
    )
    (net (code "65") (name "Net-(IC1-VDD)") (class "Default")
      (node (ref "C4") (pin "1") (pinfunction "1_1") (pintype "passive"))
      (node (ref "IC1") (pin "1") (pinfunction "VDD_1") (pintype "bidirectional"))
      (node (ref "JP1") (pin "1") (pinfunction "1_1") (pintype "passive"))
      (node (ref "R15") (pin "1") (pinfunction "1_1") (pintype "passive"))
      (node (ref "U$2") (pin "VBUS") (pinfunction "VBUS_VBUS") (pintype "bidirectional"))
      (node (ref "X1") (pin "VBUS") (pinfunction "VBUS_VBUS") (pintype "bidirectional"))
    )
    (net (code "66") (name "Net-(IC1-VUSB)") (class "Default")
      (node (ref "C3") (pin "2") (pinfunction "2_2") (pintype "passive"))
      (node (ref "IC1") (pin "17") (pinfunction "VUSB_17") (pintype "bidirectional"))
    )
    (net (code "67") (name "Net-(IC2-AREF)") (class "Default")
      (node (ref "C23") (pin "1") (pinfunction "1_1") (pintype "passive"))
      (node (ref "IC2") (pin "32") (pinfunction "AREF_32") (pintype "passive"))
    )
    (net (code "68") (name "Net-(IC2-XTAL1)") (class "Default")
      (node (ref "C6") (pin "1") (pinfunction "1_1") (pintype "passive"))
      (node (ref "IC2") (pin "13") (pinfunction "XTAL1_13") (pintype "input"))
      (node (ref "Q2") (pin "2") (pinfunction "2_2") (pintype "passive"))
    )
    (net (code "69") (name "Net-(IC2-XTAL2)") (class "Default")
      (node (ref "C5") (pin "1") (pinfunction "1_1") (pintype "passive"))
      (node (ref "IC2") (pin "12") (pinfunction "XTAL2_12") (pintype "output"))
      (node (ref "Q2") (pin "1") (pinfunction "1_1") (pintype "passive"))
    )
    (net (code "70") (name "Net-(R2-Pad1)") (class "Default")
      (node (ref "R2") (pin "1") (pinfunction "1_1") (pintype "passive"))
      (node (ref "TXLED") (pin "C") (pinfunction "C_C") (pintype "passive"))
    )
    (net (code "71") (name "Net-(R3-Pad1)") (class "Default")
      (node (ref "R3") (pin "1") (pinfunction "1_1") (pintype "passive"))
      (node (ref "RXLED") (pin "C") (pinfunction "C_C") (pintype "passive"))
    )
    (net (code "72") (name "Net-(R5-Pad1)") (class "Default")
      (node (ref "R5") (pin "1") (pinfunction "1_1") (pintype "passive"))
      (node (ref "SJ1") (pin "1") (pinfunction "1_1") (pintype "passive"))
      (node (ref "SJ2") (pin "1") (pinfunction "1_1") (pintype "passive"))
      (node (ref "XPOLOLU") (pin "MS1") (pinfunction "MS1_MS1") (pintype "input"))
    )
    (net (code "73") (name "Net-(R6-Pad1)") (class "Default")
      (node (ref "R6") (pin "1") (pinfunction "1_1") (pintype "passive"))
      (node (ref "SJ3") (pin "1") (pinfunction "1_1") (pintype "passive"))
      (node (ref "SJ4") (pin "1") (pinfunction "1_1") (pintype "passive"))
      (node (ref "YPOLOLU") (pin "MS1") (pinfunction "MS1_MS1") (pintype "input"))
    )
    (net (code "74") (name "Net-(R7-Pad1)") (class "Default")
      (node (ref "R7") (pin "1") (pinfunction "1_1") (pintype "passive"))
      (node (ref "SJ5") (pin "1") (pinfunction "1_1") (pintype "passive"))
      (node (ref "SJ6") (pin "1") (pinfunction "1_1") (pintype "passive"))
      (node (ref "ZPOLOLU") (pin "MS1") (pinfunction "MS1_MS1") (pintype "input"))
    )
    (net (code "75") (name "Net-(R15-Pad2)") (class "Default")
      (node (ref "R15") (pin "2") (pinfunction "2_2") (pintype "passive"))
      (node (ref "USBLED") (pin "A") (pinfunction "A_A") (pintype "passive"))
    )
    (net (code "76") (name "Net-(R16-Pad1)") (class "Default")
      (node (ref "R16") (pin "1") (pinfunction "1_1") (pintype "passive"))
      (node (ref "VCCOK") (pin "A") (pinfunction "A_A") (pintype "passive"))
    )
    (net (code "77") (name "Net-(SJ1-Pad2)") (class "Default")
      (node (ref "SJ1") (pin "2") (pinfunction "2_2") (pintype "passive"))
      (node (ref "XPOLOLU") (pin "MS2") (pinfunction "MS2_MS2") (pintype "input"))
    )
    (net (code "78") (name "Net-(SJ2-Pad2)") (class "Default")
      (node (ref "SJ2") (pin "2") (pinfunction "2_2") (pintype "passive"))
      (node (ref "XPOLOLU") (pin "MS3") (pinfunction "MS3_MS3") (pintype "input"))
    )
    (net (code "79") (name "Net-(SJ3-Pad2)") (class "Default")
      (node (ref "SJ3") (pin "2") (pinfunction "2_2") (pintype "passive"))
      (node (ref "YPOLOLU") (pin "MS2") (pinfunction "MS2_MS2") (pintype "input"))
    )
    (net (code "80") (name "Net-(SJ4-Pad2)") (class "Default")
      (node (ref "SJ4") (pin "2") (pinfunction "2_2") (pintype "passive"))
      (node (ref "YPOLOLU") (pin "MS3") (pinfunction "MS3_MS3") (pintype "input"))
    )
    (net (code "81") (name "Net-(SJ5-Pad2)") (class "Default")
      (node (ref "SJ5") (pin "2") (pinfunction "2_2") (pintype "passive"))
      (node (ref "ZPOLOLU") (pin "MS2") (pinfunction "MS2_MS2") (pintype "input"))
    )
    (net (code "82") (name "Net-(SJ6-Pad2)") (class "Default")
      (node (ref "SJ6") (pin "2") (pinfunction "2_2") (pintype "passive"))
      (node (ref "ZPOLOLU") (pin "MS3") (pinfunction "MS3_MS3") (pintype "input"))
    )
    (net (code "83") (name "Net-(X2A-S)") (class "Default")
      (node (ref "X2") (pin "1") (pinfunction "S_1") (pintype "passive"))
      (node (ref "XMOT1") (pin "1") (pinfunction "1_1") (pintype "passive"))
      (node (ref "XPOLOLU") (pin "2B") (pinfunction "2B_2B") (pintype "output"))
    )
    (net (code "84") (name "Net-(X2B-S)") (class "Default")
      (node (ref "X2") (pin "2") (pinfunction "S_2") (pintype "passive"))
      (node (ref "XMOT1") (pin "2") (pinfunction "2_2") (pintype "passive"))
      (node (ref "XPOLOLU") (pin "2A") (pinfunction "2A_2A") (pintype "output"))
    )
    (net (code "85") (name "Net-(X2C-S)") (class "Default")
      (node (ref "X2") (pin "3") (pinfunction "S_3") (pintype "passive"))
      (node (ref "XMOT2") (pin "1") (pinfunction "1_1") (pintype "passive"))
      (node (ref "XPOLOLU") (pin "1A") (pinfunction "1A_1A") (pintype "output"))
    )
    (net (code "86") (name "Net-(X2D-S)") (class "Default")
      (node (ref "X2") (pin "4") (pinfunction "S_4") (pintype "passive"))
      (node (ref "XMOT2") (pin "2") (pinfunction "2_2") (pintype "passive"))
      (node (ref "XPOLOLU") (pin "1B") (pinfunction "1B_1B") (pintype "output"))
    )
    (net (code "87") (name "Net-(X3A-S)") (class "Default")
      (node (ref "X3") (pin "1") (pinfunction "S_1") (pintype "passive"))
      (node (ref "YMOT1") (pin "1") (pinfunction "1_1") (pintype "passive"))
      (node (ref "YPOLOLU") (pin "2B") (pinfunction "2B_2B") (pintype "output"))
    )
    (net (code "88") (name "Net-(X3B-S)") (class "Default")
      (node (ref "X3") (pin "2") (pinfunction "S_2") (pintype "passive"))
      (node (ref "YMOT1") (pin "2") (pinfunction "2_2") (pintype "passive"))
      (node (ref "YPOLOLU") (pin "2A") (pinfunction "2A_2A") (pintype "output"))
    )
    (net (code "89") (name "Net-(X3C-S)") (class "Default")
      (node (ref "X3") (pin "3") (pinfunction "S_3") (pintype "passive"))
      (node (ref "YMOT2") (pin "1") (pinfunction "1_1") (pintype "passive"))
      (node (ref "YPOLOLU") (pin "1A") (pinfunction "1A_1A") (pintype "output"))
    )
    (net (code "90") (name "Net-(X3D-S)") (class "Default")
      (node (ref "X3") (pin "4") (pinfunction "S_4") (pintype "passive"))
      (node (ref "YMOT2") (pin "2") (pinfunction "2_2") (pintype "passive"))
      (node (ref "YPOLOLU") (pin "1B") (pinfunction "1B_1B") (pintype "output"))
    )
    (net (code "91") (name "Net-(X4A-S)") (class "Default")
      (node (ref "X4") (pin "1") (pinfunction "S_1") (pintype "passive"))
      (node (ref "ZMOT1") (pin "1") (pinfunction "1_1") (pintype "passive"))
      (node (ref "ZPOLOLU") (pin "2B") (pinfunction "2B_2B") (pintype "output"))
    )
    (net (code "92") (name "Net-(X4B-S)") (class "Default")
      (node (ref "X4") (pin "2") (pinfunction "S_2") (pintype "passive"))
      (node (ref "ZMOT1") (pin "2") (pinfunction "2_2") (pintype "passive"))
      (node (ref "ZPOLOLU") (pin "2A") (pinfunction "2A_2A") (pintype "output"))
    )
    (net (code "93") (name "Net-(X4C-S)") (class "Default")
      (node (ref "X4") (pin "3") (pinfunction "S_3") (pintype "passive"))
      (node (ref "ZMOT2") (pin "1") (pinfunction "1_1") (pintype "passive"))
      (node (ref "ZPOLOLU") (pin "1A") (pinfunction "1A_1A") (pintype "output"))
    )
    (net (code "94") (name "Net-(X4D-S)") (class "Default")
      (node (ref "X4") (pin "4") (pinfunction "S_4") (pintype "passive"))
      (node (ref "ZMOT2") (pin "2") (pinfunction "2_2") (pintype "passive"))
      (node (ref "ZPOLOLU") (pin "1B") (pinfunction "1B_1B") (pintype "output"))
    )
    (net (code "95") (name "Net-(X7A-S)") (class "Default")
      (node (ref "E1MOT1") (pin "1") (pinfunction "1_1") (pintype "passive"))
      (node (ref "EPOLOLU") (pin "2B") (pinfunction "2B_2B") (pintype "output"))
      (node (ref "X7") (pin "1") (pinfunction "S_1") (pintype "passive"))
    )
    (net (code "96") (name "Net-(X7B-S)") (class "Default")
      (node (ref "E1MOT1") (pin "2") (pinfunction "2_2") (pintype "passive"))
      (node (ref "EPOLOLU") (pin "2A") (pinfunction "2A_2A") (pintype "output"))
      (node (ref "X7") (pin "2") (pinfunction "S_2") (pintype "passive"))
    )
    (net (code "97") (name "Net-(X7C-S)") (class "Default")
      (node (ref "E1MOT2") (pin "1") (pinfunction "1_1") (pintype "passive"))
      (node (ref "EPOLOLU") (pin "1A") (pinfunction "1A_1A") (pintype "output"))
      (node (ref "X7") (pin "3") (pinfunction "S_3") (pintype "passive"))
    )
    (net (code "98") (name "Net-(X7D-S)") (class "Default")
      (node (ref "E1MOT2") (pin "2") (pinfunction "2_2") (pintype "passive"))
      (node (ref "EPOLOLU") (pin "1B") (pinfunction "1B_1B") (pintype "output"))
      (node (ref "X7") (pin "4") (pinfunction "S_4") (pintype "passive"))
    )
    (net (code "99") (name "Net-(X8A-S)") (class "Default")
      (node (ref "E2MOT1") (pin "1") (pinfunction "1_1") (pintype "passive"))
      (node (ref "EPOLOLU2") (pin "2B") (pinfunction "2B_2B") (pintype "output"))
      (node (ref "X8") (pin "1") (pinfunction "S_1") (pintype "passive"))
    )
    (net (code "100") (name "Net-(X8B-S)") (class "Default")
      (node (ref "E2MOT1") (pin "2") (pinfunction "2_2") (pintype "passive"))
      (node (ref "EPOLOLU2") (pin "2A") (pinfunction "2A_2A") (pintype "output"))
      (node (ref "X8") (pin "2") (pinfunction "S_2") (pintype "passive"))
    )
    (net (code "101") (name "Net-(X8C-S)") (class "Default")
      (node (ref "E2MOT2") (pin "1") (pinfunction "1_1") (pintype "passive"))
      (node (ref "EPOLOLU2") (pin "1A") (pinfunction "1A_1A") (pintype "output"))
      (node (ref "X8") (pin "3") (pinfunction "S_3") (pintype "passive"))
    )
    (net (code "102") (name "Net-(X8D-S)") (class "Default")
      (node (ref "E2MOT2") (pin "2") (pinfunction "2_2") (pintype "passive"))
      (node (ref "EPOLOLU2") (pin "1B") (pinfunction "1B_1B") (pintype "output"))
      (node (ref "X8") (pin "4") (pinfunction "S_4") (pintype "passive"))
    )
    (net (code "103") (name "Net-(XPOLOLU-SLEEP)") (class "Default")
      (node (ref "XPOLOLU") (pin "RST") (pinfunction "RST_RST") (pintype "input"))
      (node (ref "XPOLOLU") (pin "SLP") (pinfunction "SLEEP_SLP") (pintype "input"))
    )
    (net (code "104") (name "Net-(YPOLOLU-SLEEP)") (class "Default")
      (node (ref "YPOLOLU") (pin "RST") (pinfunction "RST_RST") (pintype "input"))
      (node (ref "YPOLOLU") (pin "SLP") (pinfunction "SLEEP_SLP") (pintype "input"))
    )
    (net (code "105") (name "Net-(ZPOLOLU-SLEEP)") (class "Default")
      (node (ref "ZPOLOLU") (pin "RST") (pinfunction "RST_RST") (pintype "input"))
      (node (ref "ZPOLOLU") (pin "SLP") (pinfunction "SLEEP_SLP") (pintype "input"))
    )
    (net (code "106") (name "VCC") (class "Default")
      (node (ref "C10") (pin "1") (pinfunction "1_1") (pintype "passive"))
      (node (ref "C11") (pin "1") (pinfunction "1_1") (pintype "passive"))
      (node (ref "C12") (pin "1") (pinfunction "1_1") (pintype "passive"))
      (node (ref "C18") (pin "1") (pinfunction "1_1") (pintype "passive"))
      (node (ref "C30") (pin "+") (pinfunction "+_+") (pintype "passive"))
      (node (ref "C8") (pin "1") (pinfunction "1_1") (pintype "passive"))
      (node (ref "C9") (pin "1") (pinfunction "1_1") (pintype "passive"))
      (node (ref "ENABLE") (pin "A") (pinfunction "A_A") (pintype "passive"))
      (node (ref "EPOLOLU") (pin "VDD") (pinfunction "VDD_VDD") (pintype "power_in"))
      (node (ref "EPOLOLU2") (pin "VDD") (pinfunction "VDD_VDD") (pintype "power_in"))
      (node (ref "IC2") (pin "10") (pinfunction "VCC_10") (pintype "power_in"))
      (node (ref "J2") (pin "2") (pinfunction "2_2") (pintype "passive"))
      (node (ref "JP1") (pin "2") (pinfunction "2_2") (pintype "passive"))
      (node (ref "L1") (pin "2") (pinfunction "2_2") (pintype "passive"))
      (node (ref "R1") (pin "2") (pinfunction "2_2") (pintype "passive"))
      (node (ref "R16") (pin "2") (pinfunction "2_2") (pintype "passive"))
      (node (ref "R4") (pin "2") (pinfunction "2_2") (pintype "passive"))
      (node (ref "R5") (pin "2") (pinfunction "2_2") (pintype "passive"))
      (node (ref "R6") (pin "2") (pinfunction "2_2") (pintype "passive"))
      (node (ref "R7") (pin "2") (pinfunction "2_2") (pintype "passive"))
      (node (ref "R8") (pin "2") (pinfunction "2_2") (pintype "passive"))
      (node (ref "R9") (pin "2") (pinfunction "2_2") (pintype "passive"))
      (node (ref "RXLED") (pin "A") (pinfunction "A_A") (pintype "passive"))
      (node (ref "TXLED") (pin "A") (pinfunction "A_A") (pintype "passive"))
      (node (ref "VREG4") (pin "2") (pinfunction "VOUT_2") (pintype "bidirectional"))
      (node (ref "XPOLOLU") (pin "VDD") (pinfunction "VDD_VDD") (pintype "power_in"))
      (node (ref "YPOLOLU") (pin "VDD") (pinfunction "VDD_VDD") (pintype "power_in"))
      (node (ref "ZPOLOLU") (pin "VDD") (pinfunction "VDD_VDD") (pintype "power_in"))
    )
    (net (code "107") (name "unconnected-(IC1-CTS-Pad13)") (class "Default")
      (node (ref "IC1") (pin "13") (pinfunction "CTS_13") (pintype "bidirectional"))
    )
    (net (code "108") (name "unconnected-(IC1-GPIO2-Pad14)") (class "Default")
      (node (ref "IC1") (pin "14") (pinfunction "GPIO2_14") (pintype "bidirectional"))
    )
    (net (code "109") (name "unconnected-(IC1-GPIO3-Pad9)") (class "Default")
      (node (ref "IC1") (pin "9") (pinfunction "GPIO3_9") (pintype "bidirectional"))
    )
    (net (code "110") (name "unconnected-(IC1-GPIO4-Pad8)") (class "Default")
      (node (ref "IC1") (pin "8") (pinfunction "GPIO4_8") (pintype "bidirectional"))
    )
    (net (code "111") (name "unconnected-(IC1-GPIO5-Pad7)") (class "Default")
      (node (ref "IC1") (pin "7") (pinfunction "GPIO5_7") (pintype "bidirectional"))
    )
    (net (code "112") (name "unconnected-(IC1-SSPND-Pad16)") (class "Default")
      (node (ref "IC1") (pin "16") (pinfunction "SSPND_16") (pintype "bidirectional"))
    )
    (net (code "113") (name "unconnected-(IC1-USBCFG-Pad15)") (class "Default")
      (node (ref "IC1") (pin "15") (pinfunction "USBCFG_15") (pintype "bidirectional"))
    )
    (net (code "114") (name "unconnected-(JP6-Pad8)") (class "Default")
      (node (ref "JP6") (pin "8") (pinfunction "8_8") (pintype "passive"))
    )
    (net (code "115") (name "unconnected-(U$2-MTN1-PadMTN3)") (class "Default")
      (node (ref "U$2") (pin "MTN3") (pinfunction "MTN1_MTN3") (pintype "bidirectional"))
    )
    (net (code "116") (name "unconnected-(U$2-MTN2-PadMTN1)") (class "Default")
      (node (ref "U$2") (pin "MTN1") (pinfunction "MTN2_MTN1") (pintype "bidirectional"))
    )
    (net (code "117") (name "unconnected-(U$2-MTN3-PadMTN2)") (class "Default")
      (node (ref "U$2") (pin "MTN2") (pinfunction "MTN3_MTN2") (pintype "bidirectional"))
    )
    (net (code "118") (name "unconnected-(U$2-PadID)") (class "Default")
      (node (ref "U$2") (pin "ID") (pinfunction "ID_ID") (pintype "bidirectional"))
    )
    (net (code "119") (name "unconnected-(U$2-PadMTN4)") (class "Default")
      (node (ref "U$2") (pin "MTN4") (pinfunction "MTN4_MTN4") (pintype "bidirectional"))
    )
  )
)
